# 00B-002.net
KiCad netlist of a schematic drawn in EAGLE
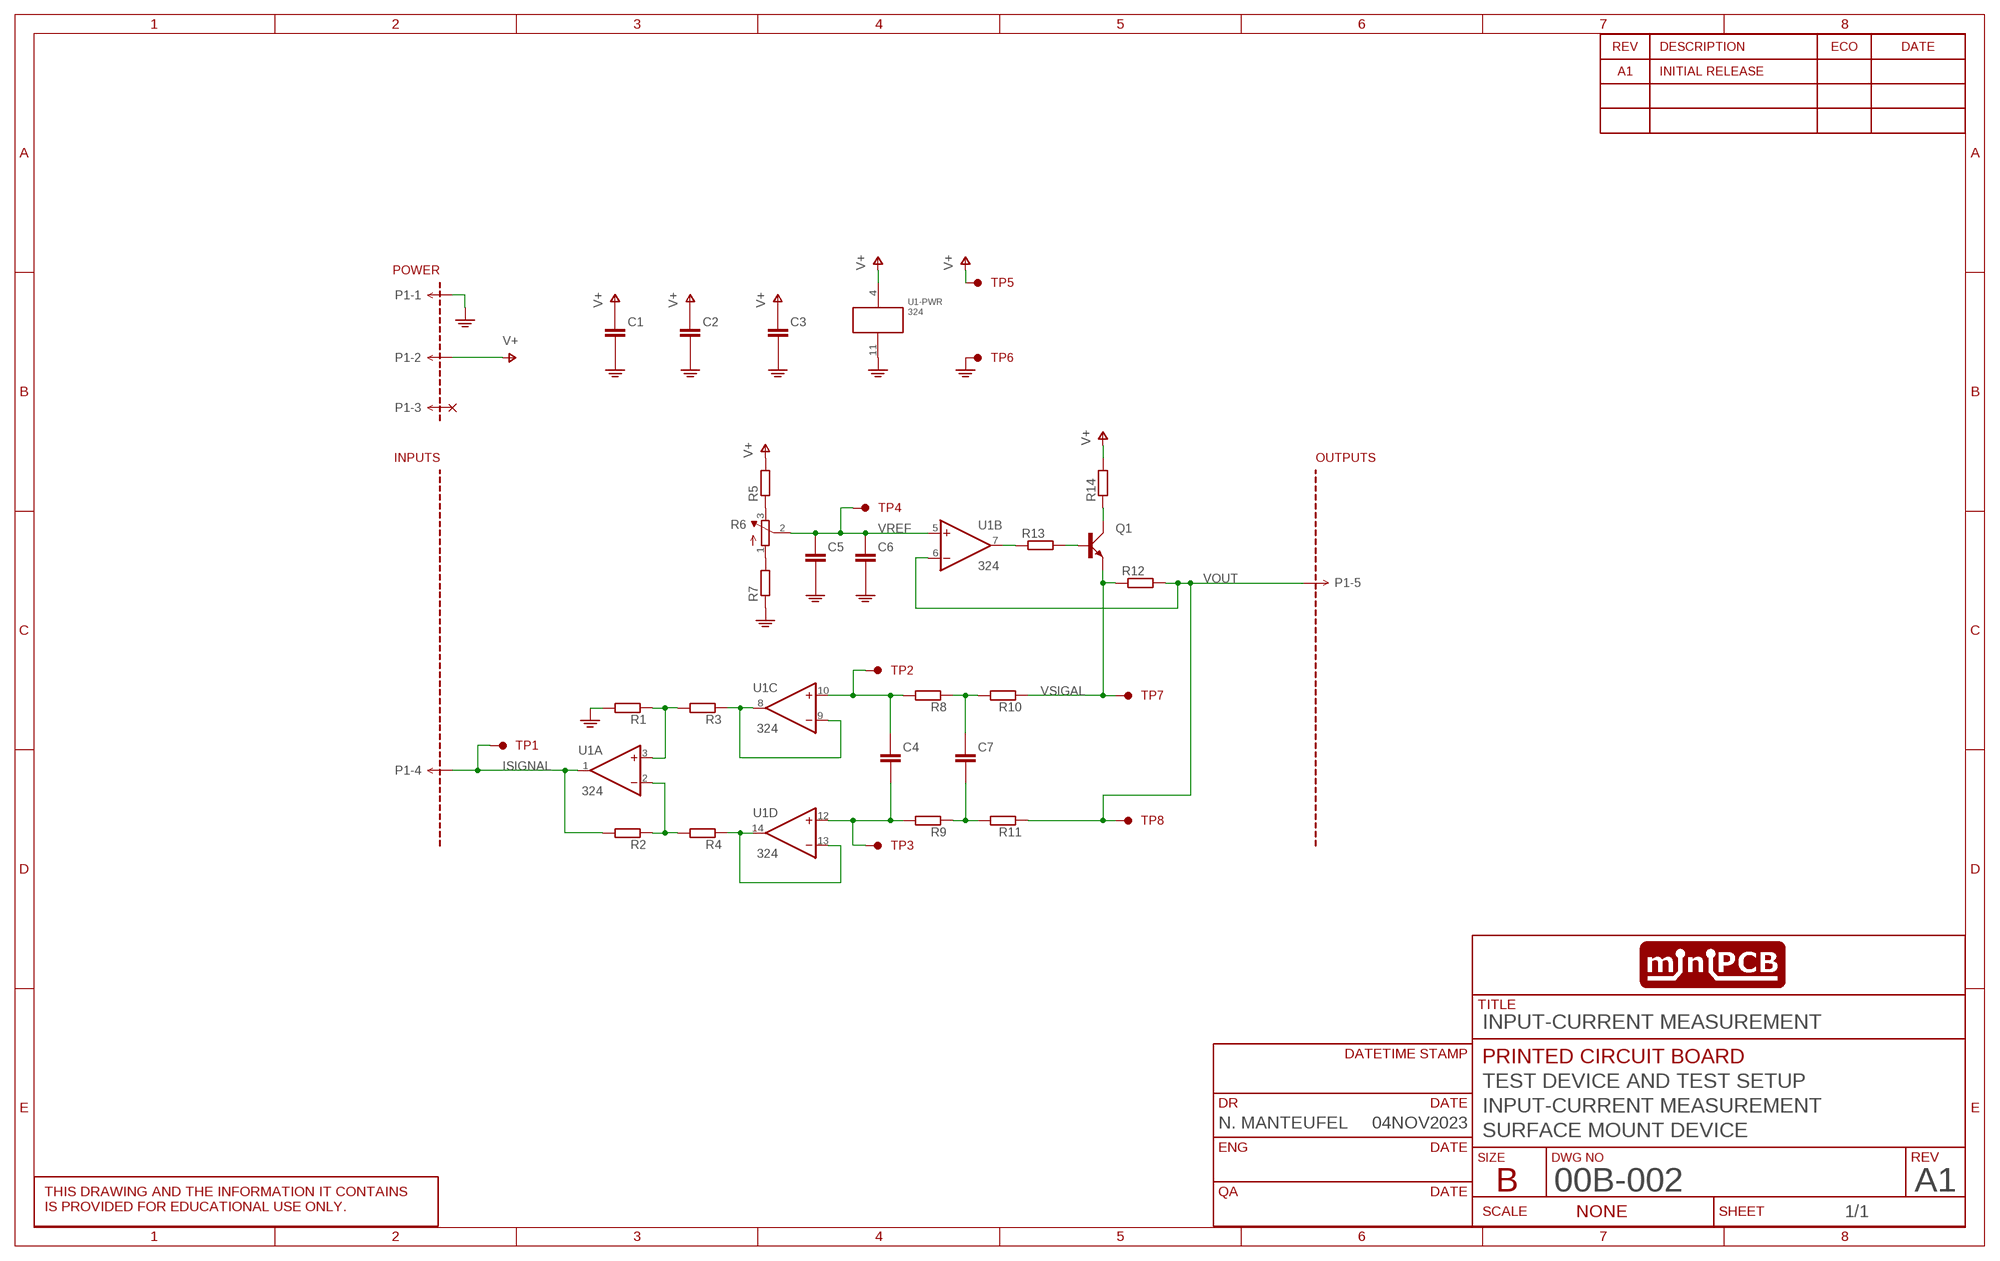
[diagram p0: schematic, sheet 1]

(export (version "E")
  (design (tool "Eeschema 10.0.6"))
  (components
    (comp (ref "C1")
      (value "1u")
      (footprint "eagle-import:C5MM")
      (libsource (lib "eagle-import") (part "CAPACITOR_10"))
    )
    (comp (ref "C2")
      (value "1u")
      (footprint "eagle-import:C0805")
      (libsource (lib "eagle-import") (part "CAPACITORSMD"))
    )
    (comp (ref "C3")
      (value "1u")
      (footprint "eagle-import:C0805")
      (libsource (lib "eagle-import") (part "CAPACITORSMD"))
    )
    (comp (ref "C4")
      (value "CAPACITORSMD")
      (footprint "eagle-import:C0805")
      (libsource (lib "eagle-import") (part "CAPACITORSMD"))
    )
    (comp (ref "C5")
      (value "CAPACITORSMD")
      (footprint "eagle-import:C0805")
      (libsource (lib "eagle-import") (part "CAPACITORSMD"))
    )
    (comp (ref "C6")
      (value "CAPACITOR_10")
      (footprint "eagle-import:C5MM")
      (libsource (lib "eagle-import") (part "CAPACITOR_10"))
    )
    (comp (ref "C7")
      (value "CAPACITORSMD")
      (footprint "eagle-import:C0805")
      (libsource (lib "eagle-import") (part "CAPACITORSMD"))
    )
    (comp (ref "P1")
      (value "MINIPCB_5P5P")
      (footprint "eagle-import:PINS_1X5")
      (libsource (lib "eagle-import") (part "MINIPCB_5P5P"))
    )
    (comp (ref "PCB1")
      (value "MINIPCB_0P33X50")
      (footprint "eagle-import:MINIPCB_0P_33X50")
      (fields
        (field (name "PART_NUMBER") "00B-002")
        (field (name "REVISION") "A1-01")
        (field (name "TITLE") "QUIESCENT CURRENT AMPLIFIER")
      )
      (libsource (lib "eagle-import") (part "MINIPCB_0P33X50"))
    )
    (comp (ref "Q1")
      (value "BJT_NPNBCE")
      (footprint "eagle-import:SOT223")
      (libsource (lib "eagle-import") (part "BJT_NPNBCE"))
    )
    (comp (ref "R1")
      (value "RESISTORSMD")
      (footprint "eagle-import:R0805")
      (libsource (lib "eagle-import") (part "RESISTORSMD"))
    )
    (comp (ref "R2")
      (value "RESISTORSMD")
      (footprint "eagle-import:R0805")
      (libsource (lib "eagle-import") (part "RESISTORSMD"))
    )
    (comp (ref "R3")
      (value "RESISTORSMD")
      (footprint "eagle-import:R0805")
      (libsource (lib "eagle-import") (part "RESISTORSMD"))
    )
    (comp (ref "R4")
      (value "RESISTORSMD")
      (footprint "eagle-import:R0805")
      (libsource (lib "eagle-import") (part "RESISTORSMD"))
    )
    (comp (ref "R5")
      (value "RESISTORSMD")
      (footprint "eagle-import:R0805")
      (libsource (lib "eagle-import") (part "RESISTORSMD"))
    )
    (comp (ref "R6")
      (value "TRIMPOT0.100THD")
      (footprint "eagle-import:TRIM_0100")
      (libsource (lib "eagle-import") (part "TRIMPOT0.100THD"))
    )
    (comp (ref "R7")
      (value "RESISTORSMD")
      (footprint "eagle-import:R0805")
      (libsource (lib "eagle-import") (part "RESISTORSMD"))
    )
    (comp (ref "R8")
      (value "RESISTORSMD")
      (footprint "eagle-import:R0805")
      (libsource (lib "eagle-import") (part "RESISTORSMD"))
    )
    (comp (ref "R9")
      (value "RESISTORSMD")
      (footprint "eagle-import:R0805")
      (libsource (lib "eagle-import") (part "RESISTORSMD"))
    )
    (comp (ref "R10")
      (value "RESISTORSMD")
      (footprint "eagle-import:R0805")
      (libsource (lib "eagle-import") (part "RESISTORSMD"))
    )
    (comp (ref "R11")
      (value "RESISTORSMD")
      (footprint "eagle-import:R0805")
      (libsource (lib "eagle-import") (part "RESISTORSMD"))
    )
    (comp (ref "R12")
      (value "RESISTORSMD")
      (footprint "eagle-import:R0805")
      (libsource (lib "eagle-import") (part "RESISTORSMD"))
    )
    (comp (ref "R13")
      (value "RESISTORSMD")
      (footprint "eagle-import:R0805")
      (libsource (lib "eagle-import") (part "RESISTORSMD"))
    )
    (comp (ref "R14")
      (value "RESISTORSMD")
      (footprint "eagle-import:R0805")
      (libsource (lib "eagle-import") (part "RESISTORSMD"))
    )
    (comp (ref "TP1")
      (value "TESTPOINTKE5000-SMTEXT")
      (footprint "eagle-import:PINS_1_TESTPOINT_KE5000_NOTEXT")
      (libsource (lib "eagle-import") (part "TESTPOINTKE5000-SMTEXT"))
    )
    (comp (ref "TP2")
      (value "TESTPOINTKE5000-SMTEXT")
      (footprint "eagle-import:PINS_1_TESTPOINT_KE5000_NOTEXT")
      (libsource (lib "eagle-import") (part "TESTPOINTKE5000-SMTEXT"))
    )
    (comp (ref "TP3")
      (value "TESTPOINTKE5000-SMTEXT")
      (footprint "eagle-import:PINS_1_TESTPOINT_KE5000_NOTEXT")
      (libsource (lib "eagle-import") (part "TESTPOINTKE5000-SMTEXT"))
    )
    (comp (ref "TP4")
      (value "TESTPOINTKE5000-SMTEXT")
      (footprint "eagle-import:PINS_1_TESTPOINT_KE5000_NOTEXT")
      (libsource (lib "eagle-import") (part "TESTPOINTKE5000-SMTEXT"))
    )
    (comp (ref "TP5")
      (value "TESTPOINTKE5000-SMTEXT")
      (footprint "eagle-import:PINS_1_TESTPOINT_KE5000_NOTEXT")
      (libsource (lib "eagle-import") (part "TESTPOINTKE5000-SMTEXT"))
    )
    (comp (ref "TP6")
      (value "TESTPOINTKE5000-SMTEXT")
      (footprint "eagle-import:PINS_1_TESTPOINT_KE5000_NOTEXT")
      (libsource (lib "eagle-import") (part "TESTPOINTKE5000-SMTEXT"))
    )
    (comp (ref "TP7")
      (value "TESTPOINTKE5000-SMTEXT")
      (footprint "eagle-import:PINS_1_TESTPOINT_KE5000_NOTEXT")
      (libsource (lib "eagle-import") (part "TESTPOINTKE5000-SMTEXT"))
    )
    (comp (ref "TP8")
      (value "TESTPOINTKE5000-SMTEXT")
      (footprint "eagle-import:PINS_1_TESTPOINT_KE5000_NOTEXT")
      (libsource (lib "eagle-import") (part "TESTPOINTKE5000-SMTEXT"))
    )
    (comp (ref "U1")
      (value "324")
      (footprint "eagle-import:SO14")
      (libsource (lib "eagle-import") (part "OPAMP_QUADSMD"))
    )
  )
  (nets
    (net (code "1") (name "/ISIGNAL") (class "Default")
      (node (ref "P1") (pin "4") (pinfunction "1_4") (pintype "bidirectional"))
      (node (ref "R2") (pin "2") (pinfunction "2_2") (pintype "passive"))
      (node (ref "TP1") (pin "1") (pinfunction "1_1") (pintype "bidirectional"))
      (node (ref "U1") (pin "1") (pinfunction "OUT_1") (pintype "output"))
    )
    (net (code "2") (name "/VOUT") (class "Default")
      (node (ref "P1") (pin "5") (pinfunction "1_5") (pintype "bidirectional"))
      (node (ref "R11") (pin "1") (pinfunction "1_1") (pintype "passive"))
      (node (ref "R12") (pin "2") (pinfunction "2_2") (pintype "passive"))
      (node (ref "TP8") (pin "1") (pinfunction "1_1") (pintype "bidirectional"))
      (node (ref "U1") (pin "6") (pinfunction "-IN_6") (pintype "input"))
    )
    (net (code "3") (name "/VREF") (class "Default")
      (node (ref "C5") (pin "1") (pinfunction "+_1") (pintype "passive"))
      (node (ref "C6") (pin "+") (pinfunction "+_+") (pintype "passive"))
      (node (ref "R6") (pin "2") (pinfunction "S_2") (pintype "passive"))
      (node (ref "TP4") (pin "1") (pinfunction "1_1") (pintype "bidirectional"))
      (node (ref "U1") (pin "5") (pinfunction "+IN_5") (pintype "input"))
    )
    (net (code "4") (name "/VSIGAL") (class "Default")
      (node (ref "Q1") (pin "3") (pinfunction "E_3") (pintype "passive"))
      (node (ref "R10") (pin "1") (pinfunction "1_1") (pintype "passive"))
      (node (ref "R12") (pin "1") (pinfunction "1_1") (pintype "passive"))
      (node (ref "TP7") (pin "1") (pinfunction "1_1") (pintype "bidirectional"))
    )
    (net (code "5") (name "GND") (class "Default")
      (node (ref "C1") (pin "-") (pinfunction "-_-") (pintype "passive"))
      (node (ref "C2") (pin "2") (pinfunction "-_2") (pintype "passive"))
      (node (ref "C3") (pin "2") (pinfunction "-_2") (pintype "passive"))
      (node (ref "C5") (pin "2") (pinfunction "-_2") (pintype "passive"))
      (node (ref "C6") (pin "-") (pinfunction "-_-") (pintype "passive"))
      (node (ref "P1") (pin "1") (pinfunction "1_1") (pintype "bidirectional"))
      (node (ref "R1") (pin "2") (pinfunction "2_2") (pintype "passive"))
      (node (ref "R7") (pin "1") (pinfunction "1_1") (pintype "passive"))
      (node (ref "TP6") (pin "1") (pinfunction "1_1") (pintype "bidirectional"))
      (node (ref "U1") (pin "11") (pinfunction "V-_11") (pintype "power_in"))
    )
    (net (code "6") (name "Net-(C4-+)") (class "Default")
      (node (ref "C4") (pin "1") (pinfunction "+_1") (pintype "passive"))
      (node (ref "R8") (pin "2") (pinfunction "2_2") (pintype "passive"))
      (node (ref "TP2") (pin "1") (pinfunction "1_1") (pintype "bidirectional"))
      (node (ref "U1") (pin "10") (pinfunction "+IN_10") (pintype "input"))
    )
    (net (code "7") (name "Net-(C4--)") (class "Default")
      (node (ref "C4") (pin "2") (pinfunction "-_2") (pintype "passive"))
      (node (ref "R9") (pin "2") (pinfunction "2_2") (pintype "passive"))
      (node (ref "TP3") (pin "1") (pinfunction "1_1") (pintype "bidirectional"))
      (node (ref "U1") (pin "12") (pinfunction "+IN_12") (pintype "input"))
    )
    (net (code "8") (name "Net-(C7-+)") (class "Default")
      (node (ref "C7") (pin "1") (pinfunction "+_1") (pintype "passive"))
      (node (ref "R10") (pin "2") (pinfunction "2_2") (pintype "passive"))
      (node (ref "R8") (pin "1") (pinfunction "1_1") (pintype "passive"))
    )
    (net (code "9") (name "Net-(C7--)") (class "Default")
      (node (ref "C7") (pin "2") (pinfunction "-_2") (pintype "passive"))
      (node (ref "R11") (pin "2") (pinfunction "2_2") (pintype "passive"))
      (node (ref "R9") (pin "1") (pinfunction "1_1") (pintype "passive"))
    )
    (net (code "10") (name "Net-(Q1-B)") (class "Default")
      (node (ref "Q1") (pin "1") (pinfunction "B_1") (pintype "passive"))
      (node (ref "R13") (pin "2") (pinfunction "2_2") (pintype "passive"))
    )
    (net (code "11") (name "Net-(Q1-C-Pad2)") (class "Default")
      (node (ref "Q1") (pin "2") (pinfunction "C_2") (pintype "passive"))
      (node (ref "Q1") (pin "4.TAB") (pinfunction "C_4.TAB") (pintype "passive"))
      (node (ref "R14") (pin "1") (pinfunction "1_1") (pintype "passive"))
    )
    (net (code "12") (name "Net-(R6-A)") (class "Default")
      (node (ref "R6") (pin "1") (pinfunction "A_1") (pintype "passive"))
      (node (ref "R7") (pin "2") (pinfunction "2_2") (pintype "passive"))
    )
    (net (code "13") (name "Net-(R6-E)") (class "Default")
      (node (ref "R5") (pin "1") (pinfunction "1_1") (pintype "passive"))
      (node (ref "R6") (pin "3") (pinfunction "E_3") (pintype "passive"))
    )
    (net (code "14") (name "Net-(U1B-+IN)") (class "Default")
      (node (ref "R1") (pin "1") (pinfunction "1_1") (pintype "passive"))
      (node (ref "R3") (pin "2") (pinfunction "2_2") (pintype "passive"))
      (node (ref "U1") (pin "3") (pinfunction "+IN_3") (pintype "input"))
    )
    (net (code "15") (name "Net-(U1B--IN)") (class "Default")
      (node (ref "R2") (pin "1") (pinfunction "1_1") (pintype "passive"))
      (node (ref "R4") (pin "2") (pinfunction "2_2") (pintype "passive"))
      (node (ref "U1") (pin "2") (pinfunction "-IN_2") (pintype "input"))
    )
    (net (code "16") (name "Net-(U1C-OUT)") (class "Default")
      (node (ref "R13") (pin "1") (pinfunction "1_1") (pintype "passive"))
      (node (ref "U1") (pin "7") (pinfunction "OUT_7") (pintype "output"))
    )
    (net (code "17") (name "Net-(U1D--IN)") (class "Default")
      (node (ref "R3") (pin "1") (pinfunction "1_1") (pintype "passive"))
      (node (ref "U1") (pin "8") (pinfunction "OUT_8") (pintype "output"))
      (node (ref "U1") (pin "9") (pinfunction "-IN_9") (pintype "input"))
    )
    (net (code "18") (name "Net-(U1E--IN)") (class "Default")
      (node (ref "R4") (pin "1") (pinfunction "1_1") (pintype "passive"))
      (node (ref "U1") (pin "13") (pinfunction "-IN_13") (pintype "input"))
      (node (ref "U1") (pin "14") (pinfunction "OUT_14") (pintype "output"))
    )
    (net (code "19") (name "V+") (class "Default")
      (node (ref "C1") (pin "+") (pinfunction "+_+") (pintype "passive"))
      (node (ref "C2") (pin "1") (pinfunction "+_1") (pintype "passive"))
      (node (ref "C3") (pin "1") (pinfunction "+_1") (pintype "passive"))
      (node (ref "P1") (pin "2") (pinfunction "1_2") (pintype "bidirectional"))
      (node (ref "R14") (pin "2") (pinfunction "2_2") (pintype "passive"))
      (node (ref "R5") (pin "2") (pinfunction "2_2") (pintype "passive"))
      (node (ref "TP5") (pin "1") (pinfunction "1_1") (pintype "bidirectional"))
      (node (ref "U1") (pin "4") (pinfunction "V+_4") (pintype "power_in"))
    )
    (net (code "20") (name "unconnected-(P1C-1-Pad3)") (class "Default")
      (node (ref "P1") (pin "3") (pinfunction "1_3") (pintype "bidirectional"))
    )
  )
)
